# 3_phase_rectifier_reverse_protection.net
KiCad netlist of a schematic drawn in EAGLE
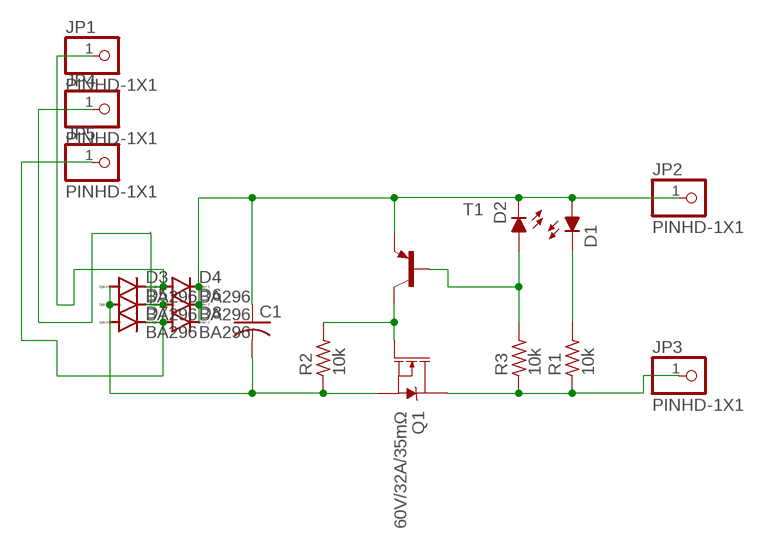
[diagram p0: schematic, sheet 1]

(export (version "E")
  (design (tool "Eeschema 10.0.6"))
  (components
    (comp (ref "C1")
      (value "C-US025-024X044")
      (footprint "eagle-import:C025-024X044")
      (libsource (lib "eagle-import") (part "C-US025-024X044"))
    )
    (comp (ref "D1")
      (value "LED_LEDCHIP-LED0603MP")
      (footprint "eagle-import:LED_CHIP-LED0603MP")
      (libsource (lib "eagle-import") (part "LED_LEDCHIP-LED0603MP"))
    )
    (comp (ref "D2")
      (value "LED_LEDCHIP-LED0603MP")
      (footprint "eagle-import:LED_CHIP-LED0603MP")
      (libsource (lib "eagle-import") (part "LED_LEDCHIP-LED0603MP"))
    )
    (comp (ref "D3")
      (value "BA296")
      (footprint "eagle-import:P2-15")
      (libsource (lib "eagle-import") (part "BA296"))
    )
    (comp (ref "D4")
      (value "BA296")
      (footprint "eagle-import:P2-15")
      (libsource (lib "eagle-import") (part "BA296"))
    )
    (comp (ref "D5")
      (value "BA296")
      (footprint "eagle-import:P2-15")
      (libsource (lib "eagle-import") (part "BA296"))
    )
    (comp (ref "D6")
      (value "BA296")
      (footprint "eagle-import:P2-15")
      (libsource (lib "eagle-import") (part "BA296"))
    )
    (comp (ref "D7")
      (value "BA296")
      (footprint "eagle-import:P2-15")
      (libsource (lib "eagle-import") (part "BA296"))
    )
    (comp (ref "D8")
      (value "BA296")
      (footprint "eagle-import:P2-15")
      (libsource (lib "eagle-import") (part "BA296"))
    )
    (comp (ref "JP1")
      (value "PINHD-1X1")
      (footprint "eagle-import:1X01")
      (libsource (lib "eagle-import") (part "PINHD-1X1"))
    )
    (comp (ref "JP2")
      (value "PINHD-1X1")
      (footprint "eagle-import:1X01")
      (libsource (lib "eagle-import") (part "PINHD-1X1"))
    )
    (comp (ref "JP3")
      (value "PINHD-1X1")
      (footprint "eagle-import:1X01")
      (libsource (lib "eagle-import") (part "PINHD-1X1"))
    )
    (comp (ref "JP4")
      (value "PINHD-1X1")
      (footprint "eagle-import:1X01")
      (libsource (lib "eagle-import") (part "PINHD-1X1"))
    )
    (comp (ref "JP5")
      (value "PINHD-1X1")
      (footprint "eagle-import:1X01")
      (libsource (lib "eagle-import") (part "PINHD-1X1"))
    )
    (comp (ref "Q1")
      (value "60V/32A/35mΩ")
      (footprint "eagle-import:TO220V")
      (libsource (lib "eagle-import") (part "MOSFET-NCH-FQP30N06L"))
    )
    (comp (ref "R1")
      (value "10k")
      (footprint "eagle-import:RC-MASTER-SMD_R0603MP")
      (libsource (lib "eagle-import") (part "RC-MASTER-SMD_R_0603MP"))
    )
    (comp (ref "R2")
      (value "10k")
      (footprint "eagle-import:RC-MASTER-SMD_R0603MP")
      (libsource (lib "eagle-import") (part "RC-MASTER-SMD_R_0603MP"))
    )
    (comp (ref "R3")
      (value "10k")
      (footprint "eagle-import:RC-MASTER-SMD_R0603MP")
      (libsource (lib "eagle-import") (part "RC-MASTER-SMD_R_0603MP"))
    )
    (comp (ref "T1")
      (value "-PNP-SC59-BEC")
      (footprint "eagle-import:SC59-BEC")
      (libsource (lib "eagle-import") (part "-PNP-SC59-BEC"))
    )
  )
  (nets
    (net (code "1") (name "Net-(C1-Pad1)") (class "Default")
      (node (ref "C1") (pin "1") (pinfunction "1_1") (pintype "passive"))
      (node (ref "D1") (pin "A") (pinfunction "A_A") (pintype "passive"))
      (node (ref "D2") (pin "C") (pinfunction "C_C") (pintype "passive"))
      (node (ref "D4") (pin "C") (pinfunction "C_C") (pintype "passive"))
      (node (ref "D6") (pin "C") (pinfunction "C_C") (pintype "passive"))
      (node (ref "D8") (pin "C") (pinfunction "C_C") (pintype "passive"))
      (node (ref "JP2") (pin "1") (pinfunction "1_1") (pintype "passive"))
      (node (ref "T1") (pin "E") (pinfunction "E_E") (pintype "passive"))
    )
    (net (code "2") (name "Net-(D1-PadC)") (class "Default")
      (node (ref "D1") (pin "C") (pinfunction "C_C") (pintype "passive"))
      (node (ref "R1") (pin "2") (pinfunction "2_2") (pintype "passive"))
    )
    (net (code "3") (name "Net-(D2-PadA)") (class "Default")
      (node (ref "D2") (pin "A") (pinfunction "A_A") (pintype "passive"))
      (node (ref "R3") (pin "2") (pinfunction "2_2") (pintype "passive"))
      (node (ref "T1") (pin "B") (pinfunction "B_B") (pintype "passive"))
    )
    (net (code "4") (name "Net-(D3-PadC)") (class "Default")
      (node (ref "D3") (pin "C") (pinfunction "C_C") (pintype "passive"))
      (node (ref "D4") (pin "A") (pinfunction "A_A") (pintype "passive"))
      (node (ref "JP1") (pin "1") (pinfunction "1_1") (pintype "passive"))
    )
    (net (code "5") (name "Net-(D5-PadC)") (class "Default")
      (node (ref "D5") (pin "C") (pinfunction "C_C") (pintype "passive"))
      (node (ref "D6") (pin "A") (pinfunction "A_A") (pintype "passive"))
      (node (ref "JP4") (pin "1") (pinfunction "1_1") (pintype "passive"))
    )
    (net (code "6") (name "Net-(D7-PadC)") (class "Default")
      (node (ref "D7") (pin "C") (pinfunction "C_C") (pintype "passive"))
      (node (ref "D8") (pin "A") (pinfunction "A_A") (pintype "passive"))
      (node (ref "JP5") (pin "1") (pinfunction "1_1") (pintype "passive"))
    )
    (net (code "7") (name "Net-(Q1-D)") (class "Default")
      (node (ref "JP3") (pin "1") (pinfunction "1_1") (pintype "passive"))
      (node (ref "Q1") (pin "2") (pinfunction "D_2") (pintype "bidirectional"))
      (node (ref "R1") (pin "1") (pinfunction "1_1") (pintype "passive"))
      (node (ref "R3") (pin "1") (pinfunction "1_1") (pintype "passive"))
    )
    (net (code "8") (name "Net-(Q1-G)") (class "Default")
      (node (ref "Q1") (pin "1") (pinfunction "G_1") (pintype "bidirectional"))
      (node (ref "R2") (pin "2") (pinfunction "2_2") (pintype "passive"))
      (node (ref "T1") (pin "C") (pinfunction "C_C") (pintype "passive"))
    )
    (net (code "9") (name "Net-(Q1-S)") (class "Default")
      (node (ref "C1") (pin "2") (pinfunction "2_2") (pintype "passive"))
      (node (ref "D3") (pin "A") (pinfunction "A_A") (pintype "passive"))
      (node (ref "D5") (pin "A") (pinfunction "A_A") (pintype "passive"))
      (node (ref "D7") (pin "A") (pinfunction "A_A") (pintype "passive"))
      (node (ref "Q1") (pin "3") (pinfunction "S_3") (pintype "bidirectional"))
      (node (ref "R2") (pin "1") (pinfunction "1_1") (pintype "passive"))
    )
  )
)
